# Sheet1.net
KiCad netlist of a schematic drawn in Altium Designer
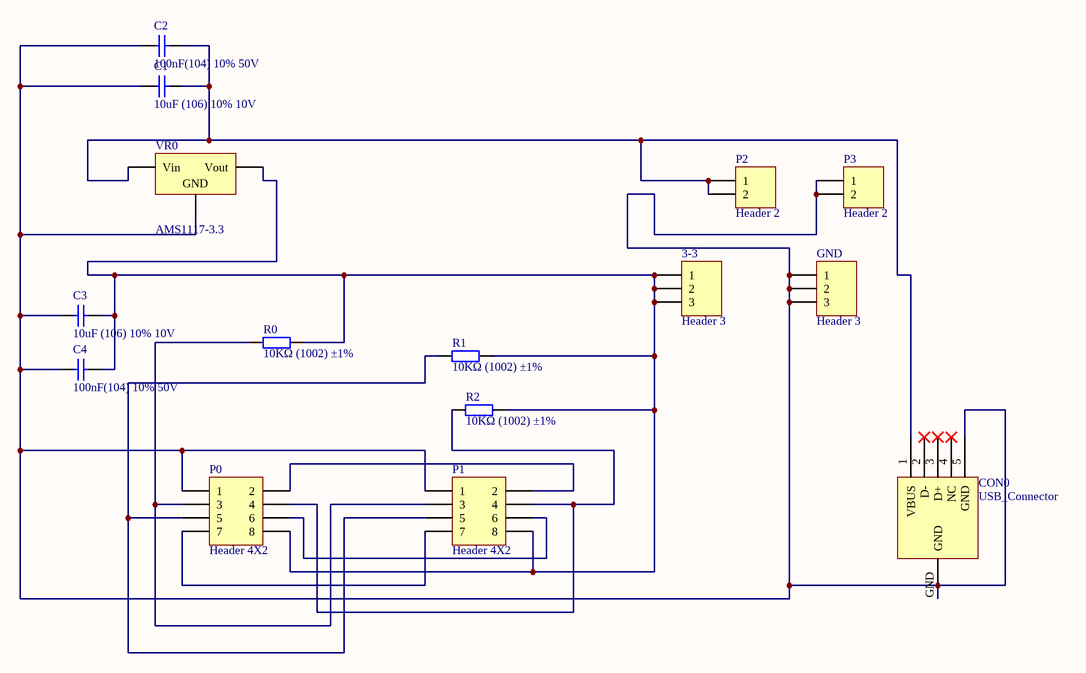
[diagram p0: Sheet1.SchDoc]

(export (version "E")
  (design (tool "Eeschema 10.0.6"))
  (components
    (comp (ref "3-3")
      (value "Header 3")
      (footprint "HDR1X3")
      (description "Header, 3-Pin")
      (fields (field (name "PUBLISHER") "Altium Limited"))
      (libsource (lib "Miscellaneous Connectors") (part "Header 3"))
    )
    (comp (ref "C1")
      (value "10uF (106) 10% 10V")
      (footprint "LC-0603_C")
      (description "贴片电容")
      (libsource (lib "Miscellaneous Devices LC") (part "0603 10uF (106) 10% 10V"))
    )
    (comp (ref "C2")
      (value "100nF(104) 10% 50V")
      (footprint "LC-0805_C")
      (description "贴片电容")
      (libsource (lib "Miscellaneous Devices LC") (part "0805 100nF(104) 10% 50V"))
    )
    (comp (ref "C3")
      (value "10uF (106) 10% 10V")
      (footprint "LC-0603_C")
      (description "贴片电容")
      (libsource (lib "Miscellaneous Devices LC") (part "0603 10uF (106) 10% 10V"))
    )
    (comp (ref "C4")
      (value "100nF(104) 10% 50V")
      (footprint "LC-0805_C")
      (description "贴片电容")
      (libsource (lib "Miscellaneous Devices LC") (part "0805 100nF(104) 10% 50V"))
    )
    (comp (ref "CON0")
      (value "USB_Connector")
      (footprint "MicroUSB")
      (libsource (lib "Mylib") (part "USB_Connector"))
    )
    (comp (ref "GND")
      (value "Header 3")
      (footprint "HDR1X3")
      (description "Header, 3-Pin")
      (fields (field (name "PUBLISHER") "Altium Limited"))
      (libsource (lib "Miscellaneous Connectors") (part "Header 3"))
    )
    (comp (ref "P0")
      (value "Header 4X2")
      (footprint "HDR2X4")
      (description "Header, 4-Pin, Dual row")
      (fields (field (name "PUBLISHER") "Altium Limited"))
      (libsource (lib "Miscellaneous Connectors") (part "Header 4X2"))
    )
    (comp (ref "P1")
      (value "Header 4X2")
      (footprint "HDR2X4")
      (description "Header, 4-Pin, Dual row")
      (fields (field (name "PUBLISHER") "Altium Limited"))
      (libsource (lib "Miscellaneous Connectors") (part "Header 4X2"))
    )
    (comp (ref "P2")
      (value "Header 2")
      (footprint "HDR1X2")
      (description "Header, 2-Pin")
      (fields (field (name "PUBLISHER") "Altium Limited"))
      (libsource (lib "Miscellaneous Connectors") (part "Header 2"))
    )
    (comp (ref "P3")
      (value "Header 2")
      (footprint "HDR1X2")
      (description "Header, 2-Pin")
      (fields (field (name "PUBLISHER") "Altium Limited"))
      (libsource (lib "Miscellaneous Connectors") (part "Header 2"))
    )
    (comp (ref "R0")
      (value "10KΩ (1002) ±1%")
      (footprint "LC-0805_R")
      (description "贴片电阻")
      (libsource (lib "Miscellaneous Devices LC") (part "0805 10KΩ (1002) 1%"))
    )
    (comp (ref "R1")
      (value "10KΩ (1002) ±1%")
      (footprint "LC-0805_R")
      (description "贴片电阻")
      (libsource (lib "Miscellaneous Devices LC") (part "0805 10KΩ (1002) 1%"))
    )
    (comp (ref "R2")
      (value "10KΩ (1002) ±1%")
      (footprint "LC-0805_R")
      (description "贴片电阻")
      (libsource (lib "Miscellaneous Devices LC") (part "0805 10KΩ (1002) 1%"))
    )
    (comp (ref "VR0")
      (value "AMS1117-3.3")
      (footprint "LC-SOT-223")
      (description "低压差线性稳压(LDO)")
      (libsource (lib "Miscellaneous Devices LC") (part "SOT-223 AMS1117-3.3"))
    )
  )
  (nets
    (net (code "1") (name "Net-(CON0-VBUS)") (class "Default")
      (node (ref "C1") (pin "2") (pinfunction "2_2") (pintype "passive"))
      (node (ref "C2") (pin "2") (pinfunction "2_2") (pintype "passive"))
      (node (ref "CON0") (pin "1") (pinfunction "VBUS_1") (pintype "passive"))
      (node (ref "P2") (pin "1") (pinfunction "1_1") (pintype "passive"))
      (node (ref "P2") (pin "2") (pinfunction "2_2") (pintype "passive"))
      (node (ref "VR0") (pin "3") (pinfunction "Vin_3") (pintype "passive"))
    )
    (net (code "2") (name "Net-(P0-Pad2)") (class "Default")
      (node (ref "P0") (pin "2") (pinfunction "2_2") (pintype "passive"))
      (node (ref "P1") (pin "2") (pinfunction "2_2") (pintype "passive"))
    )
    (net (code "3") (name "Net-(P0-Pad3)") (class "Default")
      (node (ref "P0") (pin "3") (pinfunction "3_3") (pintype "passive"))
      (node (ref "P1") (pin "3") (pinfunction "3_3") (pintype "passive"))
      (node (ref "R0") (pin "1") (pinfunction "1_1") (pintype "passive"))
    )
    (net (code "4") (name "Net-(P0-Pad4)") (class "Default")
      (node (ref "P0") (pin "4") (pinfunction "4_4") (pintype "passive"))
      (node (ref "P1") (pin "4") (pinfunction "4_4") (pintype "passive"))
      (node (ref "R2") (pin "1") (pinfunction "1_1") (pintype "passive"))
    )
    (net (code "5") (name "Net-(P0-Pad5)") (class "Default")
      (node (ref "P0") (pin "5") (pinfunction "5_5") (pintype "passive"))
      (node (ref "P1") (pin "5") (pinfunction "5_5") (pintype "passive"))
      (node (ref "R1") (pin "1") (pinfunction "1_1") (pintype "passive"))
    )
    (net (code "6") (name "Net-(P0-Pad6)") (class "Default")
      (node (ref "P0") (pin "6") (pinfunction "6_6") (pintype "passive"))
      (node (ref "P1") (pin "6") (pinfunction "6_6") (pintype "passive"))
    )
    (net (code "7") (name "Net-(P0-Pad7)") (class "Default")
      (node (ref "P0") (pin "7") (pinfunction "7_7") (pintype "passive"))
      (node (ref "P1") (pin "7") (pinfunction "7_7") (pintype "passive"))
    )
    (net (code "8") (name "Net-(VR0-GND)") (class "Default")
      (node (ref "C1") (pin "1") (pinfunction "1_1") (pintype "passive"))
      (node (ref "C2") (pin "1") (pinfunction "1_1") (pintype "passive"))
      (node (ref "C3") (pin "1") (pinfunction "1_1") (pintype "passive"))
      (node (ref "C4") (pin "1") (pinfunction "1_1") (pintype "passive"))
      (node (ref "CON0") (pin "5") (pinfunction "GND_5") (pintype "passive"))
      (node (ref "CON0") (pin "GND") (pinfunction "GND_GND") (pintype "passive"))
      (node (ref "GND") (pin "1") (pinfunction "1_1") (pintype "passive"))
      (node (ref "GND") (pin "2") (pinfunction "2_2") (pintype "passive"))
      (node (ref "GND") (pin "3") (pinfunction "3_3") (pintype "passive"))
      (node (ref "P0") (pin "1") (pinfunction "1_1") (pintype "passive"))
      (node (ref "P1") (pin "1") (pinfunction "1_1") (pintype "passive"))
      (node (ref "P3") (pin "1") (pinfunction "1_1") (pintype "passive"))
      (node (ref "P3") (pin "2") (pinfunction "2_2") (pintype "passive"))
      (node (ref "VR0") (pin "1") (pinfunction "GND_1") (pintype "passive"))
    )
    (net (code "9") (name "Net-(VR0-Vout)") (class "Default")
      (node (ref "3-3") (pin "1") (pinfunction "1_1") (pintype "passive"))
      (node (ref "3-3") (pin "2") (pinfunction "2_2") (pintype "passive"))
      (node (ref "3-3") (pin "3") (pinfunction "3_3") (pintype "passive"))
      (node (ref "C3") (pin "2") (pinfunction "2_2") (pintype "passive"))
      (node (ref "C4") (pin "2") (pinfunction "2_2") (pintype "passive"))
      (node (ref "P0") (pin "8") (pinfunction "8_8") (pintype "passive"))
      (node (ref "P1") (pin "8") (pinfunction "8_8") (pintype "passive"))
      (node (ref "R0") (pin "2") (pinfunction "2_2") (pintype "passive"))
      (node (ref "R1") (pin "2") (pinfunction "2_2") (pintype "passive"))
      (node (ref "R2") (pin "2") (pinfunction "2_2") (pintype "passive"))
      (node (ref "VR0") (pin "2") (pinfunction "Vout_2") (pintype "passive"))
    )
    (net (code "10") (name "unconnected-(CON0-D+-Pad3)") (class "Default")
      (node (ref "CON0") (pin "3") (pinfunction "D+_3") (pintype "passive+no_connect"))
    )
    (net (code "11") (name "unconnected-(CON0-D--Pad2)") (class "Default")
      (node (ref "CON0") (pin "2") (pinfunction "D-_2") (pintype "passive+no_connect"))
    )
    (net (code "12") (name "unconnected-(CON0-NC-Pad4)") (class "Default")
      (node (ref "CON0") (pin "4") (pinfunction "NC_4") (pintype "passive+no_connect"))
    )
  )
)
